# Digit_Board_add.net
KiCad netlist of a schematic drawn in Altium Designer
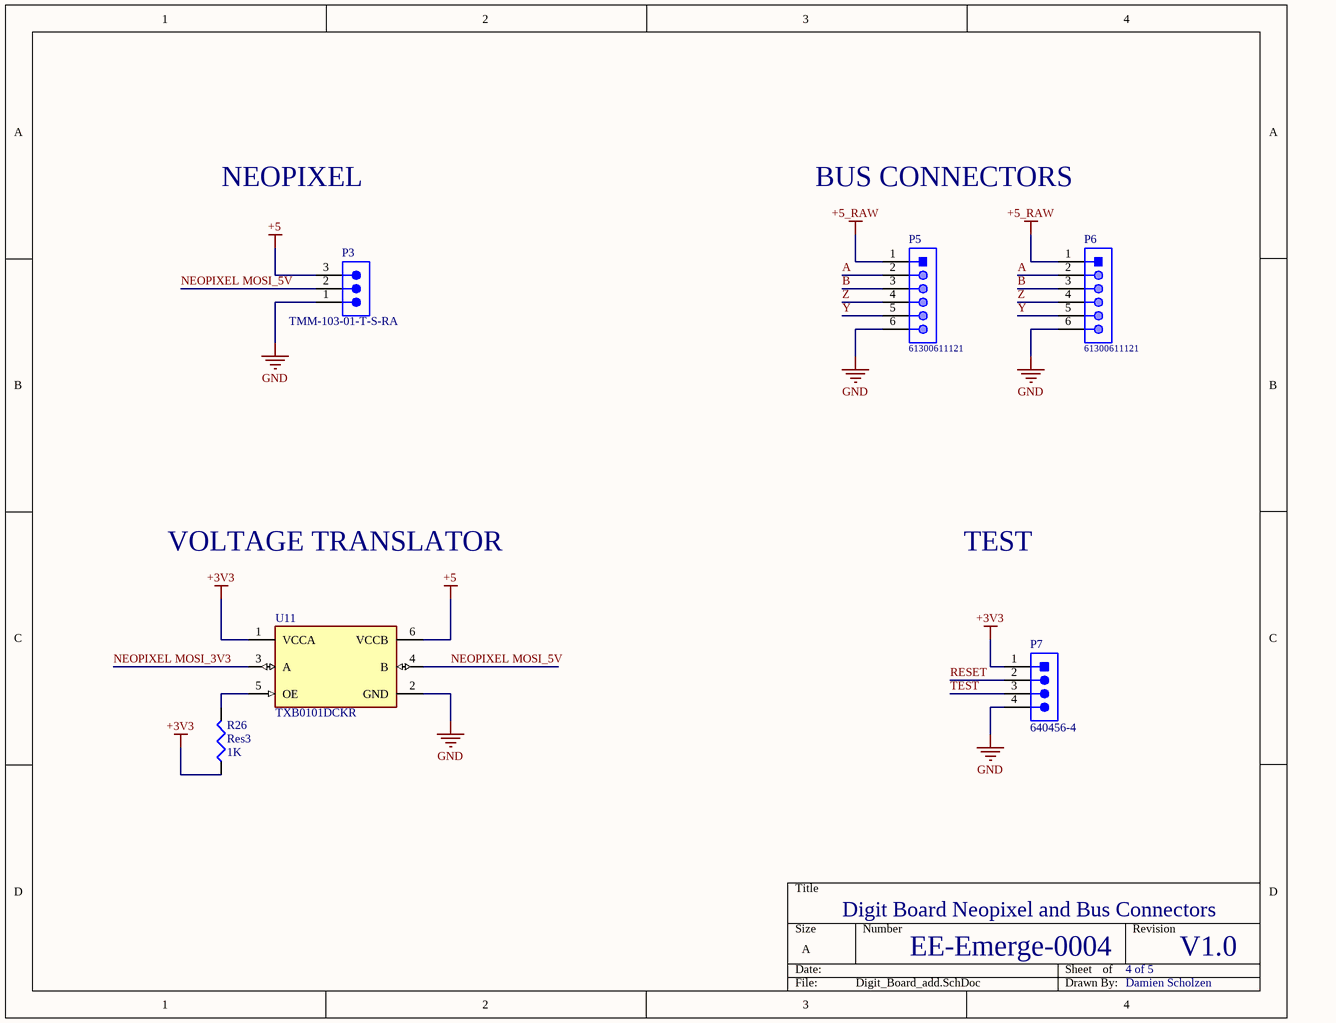
[diagram p0: Digit_Board_add.SchDoc]

(export (version "E")
  (design (tool "Eeschema 10.0.6"))
  (components
    (comp (ref "P3")
      (value "TMM-103-01-T-S-RA")
      (footprint "SMTC-TMM-103-01-X-S-RA")
      (description "Low Profile Through-Hole Header, Right Angle, -55 to 105 degC, 2 mm Pitch, 3-Pin, Male, RoHS")
      (fields (field (name "MANUFACTURER") "Samtec"))
      (libsource (lib "EE_Emerge_SkillsProject (1)") (part "CMP-1029-00176-1"))
    )
    (comp (ref "P5")
      (value "61300611121")
      (footprint "61300611121")
      (description "THT Vertical Pin Header WR-PHD, Pitch 2.54 mm, Single Row, 6 pins")
      (fields (field (name "MANUFACTURER") "Wurth Elektronik") (field (name "PUBLISHER") "WurthElektronik"))
      (libsource (lib "Altium Content Vault") (part "WE-CN-1P-M-R6"))
    )
    (comp (ref "P6")
      (value "61300611121")
      (footprint "61300611121")
      (description "THT Vertical Pin Header WR-PHD, Pitch 2.54 mm, Single Row, 6 pins")
      (fields (field (name "MANUFACTURER") "Wurth Elektronik") (field (name "PUBLISHER") "WurthElektronik"))
      (libsource (lib "Altium Content Vault") (part "WE-CN-1P-M-R6"))
    )
    (comp (ref "P7")
      (value "640456-4")
      (footprint "TECO-640456-4")
      (description "Male Header, Pitch 2.54 mm, 1 x 4 Position, Height 10.03 mm, Tail Length 3.56 mm, RoHS, Bulk")
      (fields (field (name "MANUFACTURER") "TE Connectivity"))
      (libsource (lib "Altium Content Vault") (part "CN-1P-M-R4"))
    )
    (comp (ref "R26")
      (value "Res3")
      (footprint "6-0805_N")
      (description "Resistor")
      (fields (field (name "ALTIUM_VALUE") "1K") (field (name "PUBLISHER") "Altium Limited"))
      (libsource (lib "EE_Emerge_SkillsProject (1)") (part "Res3_2"))
    )
    (comp (ref "U11")
      (value "TXB0101DCKR")
      (footprint "FP-DCK0006A-MFG")
      (description "IC TRNSLTR BIDIRECTIONAL SC70-6")
      (libsource (lib "Altium Content Vault") (part "823f5b8d9890e23408fb6963d223ccc"))
    )
  )
  (nets
    (net (code "1") (name "+3V3") (class "Default")
      (node (ref "P7") (pin "1") (pinfunction "1_1") (pintype "passive"))
      (node (ref "R26") (pin "1") (pinfunction "1_1") (pintype "passive"))
      (node (ref "U11") (pin "1") (pinfunction "VCCA_1") (pintype "power_in"))
    )
    (net (code "2") (name "+5") (class "Default")
      (node (ref "P3") (pin "3") (pinfunction "3_3") (pintype "passive"))
      (node (ref "U11") (pin "6") (pinfunction "VCCB_6") (pintype "power_in"))
    )
    (net (code "3") (name "+5_RAW") (class "Default")
      (node (ref "P5") (pin "1") (pinfunction "1_1") (pintype "passive"))
      (node (ref "P6") (pin "1") (pinfunction "1_1") (pintype "passive"))
    )
    (net (code "4") (name "/A") (class "Default")
      (node (ref "P5") (pin "2") (pinfunction "2_2") (pintype "passive"))
      (node (ref "P6") (pin "2") (pinfunction "2_2") (pintype "passive"))
    )
    (net (code "5") (name "/B") (class "Default")
      (node (ref "P5") (pin "3") (pinfunction "3_3") (pintype "passive"))
      (node (ref "P6") (pin "3") (pinfunction "3_3") (pintype "passive"))
    )
    (net (code "6") (name "/NEOPIXEL MOSI_3V3") (class "Default")
      (node (ref "U11") (pin "3") (pinfunction "A_3") (pintype "bidirectional"))
    )
    (net (code "7") (name "/NEOPIXEL MOSI_5V") (class "Default")
      (node (ref "P3") (pin "2") (pinfunction "2_2") (pintype "passive"))
      (node (ref "U11") (pin "4") (pinfunction "B_4") (pintype "bidirectional"))
    )
    (net (code "8") (name "/RESET") (class "Default")
      (node (ref "P7") (pin "2") (pinfunction "2_2") (pintype "passive"))
    )
    (net (code "9") (name "/TEST") (class "Default")
      (node (ref "P7") (pin "3") (pinfunction "3_3") (pintype "passive"))
    )
    (net (code "10") (name "/Y") (class "Default")
      (node (ref "P5") (pin "5") (pinfunction "5_5") (pintype "passive"))
      (node (ref "P6") (pin "5") (pinfunction "5_5") (pintype "passive"))
    )
    (net (code "11") (name "/Z") (class "Default")
      (node (ref "P5") (pin "4") (pinfunction "4_4") (pintype "passive"))
      (node (ref "P6") (pin "4") (pinfunction "4_4") (pintype "passive"))
    )
    (net (code "12") (name "GND") (class "Default")
      (node (ref "P3") (pin "1") (pinfunction "1_1") (pintype "passive"))
      (node (ref "P5") (pin "6") (pinfunction "6_6") (pintype "passive"))
      (node (ref "P6") (pin "6") (pinfunction "6_6") (pintype "passive"))
      (node (ref "P7") (pin "4") (pinfunction "4_4") (pintype "passive"))
      (node (ref "U11") (pin "2") (pinfunction "GND_2") (pintype "power_in"))
    )
    (net (code "13") (name "Net-(U11-OE)") (class "Default")
      (node (ref "R26") (pin "2") (pinfunction "2_2") (pintype "passive"))
      (node (ref "U11") (pin "5") (pinfunction "OE_5") (pintype "input"))
    )
  )
)
